# EMI_Shielding_Test.net
KiCad netlist of a schematic drawn in EAGLE
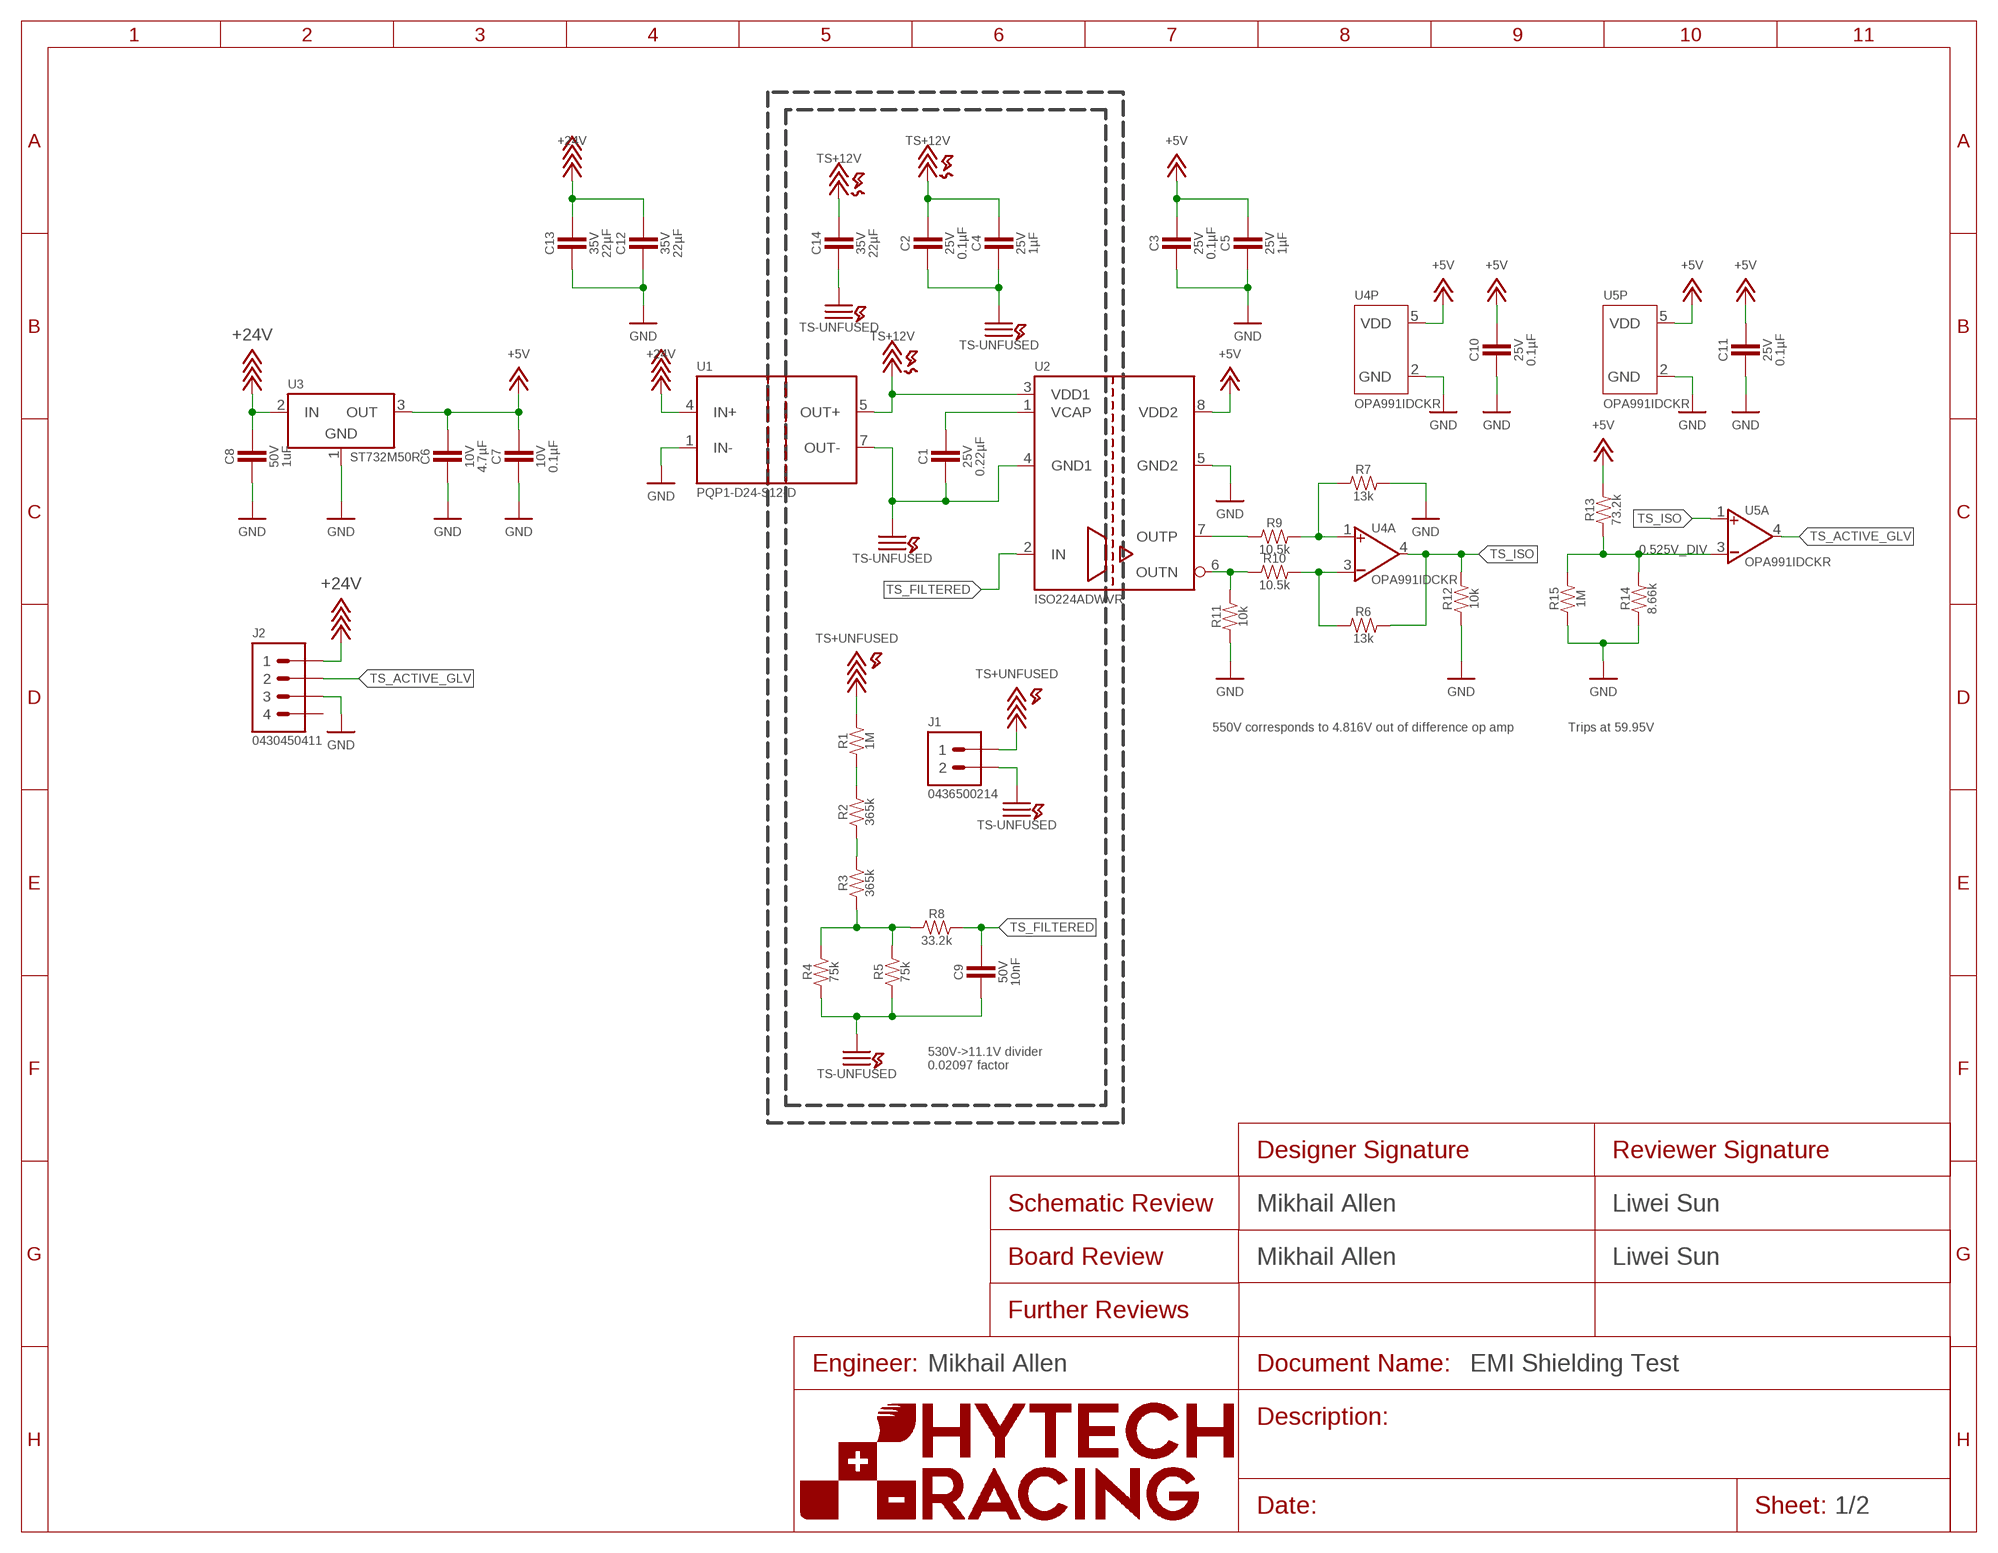
[diagram p0: schematic, sheet 1]
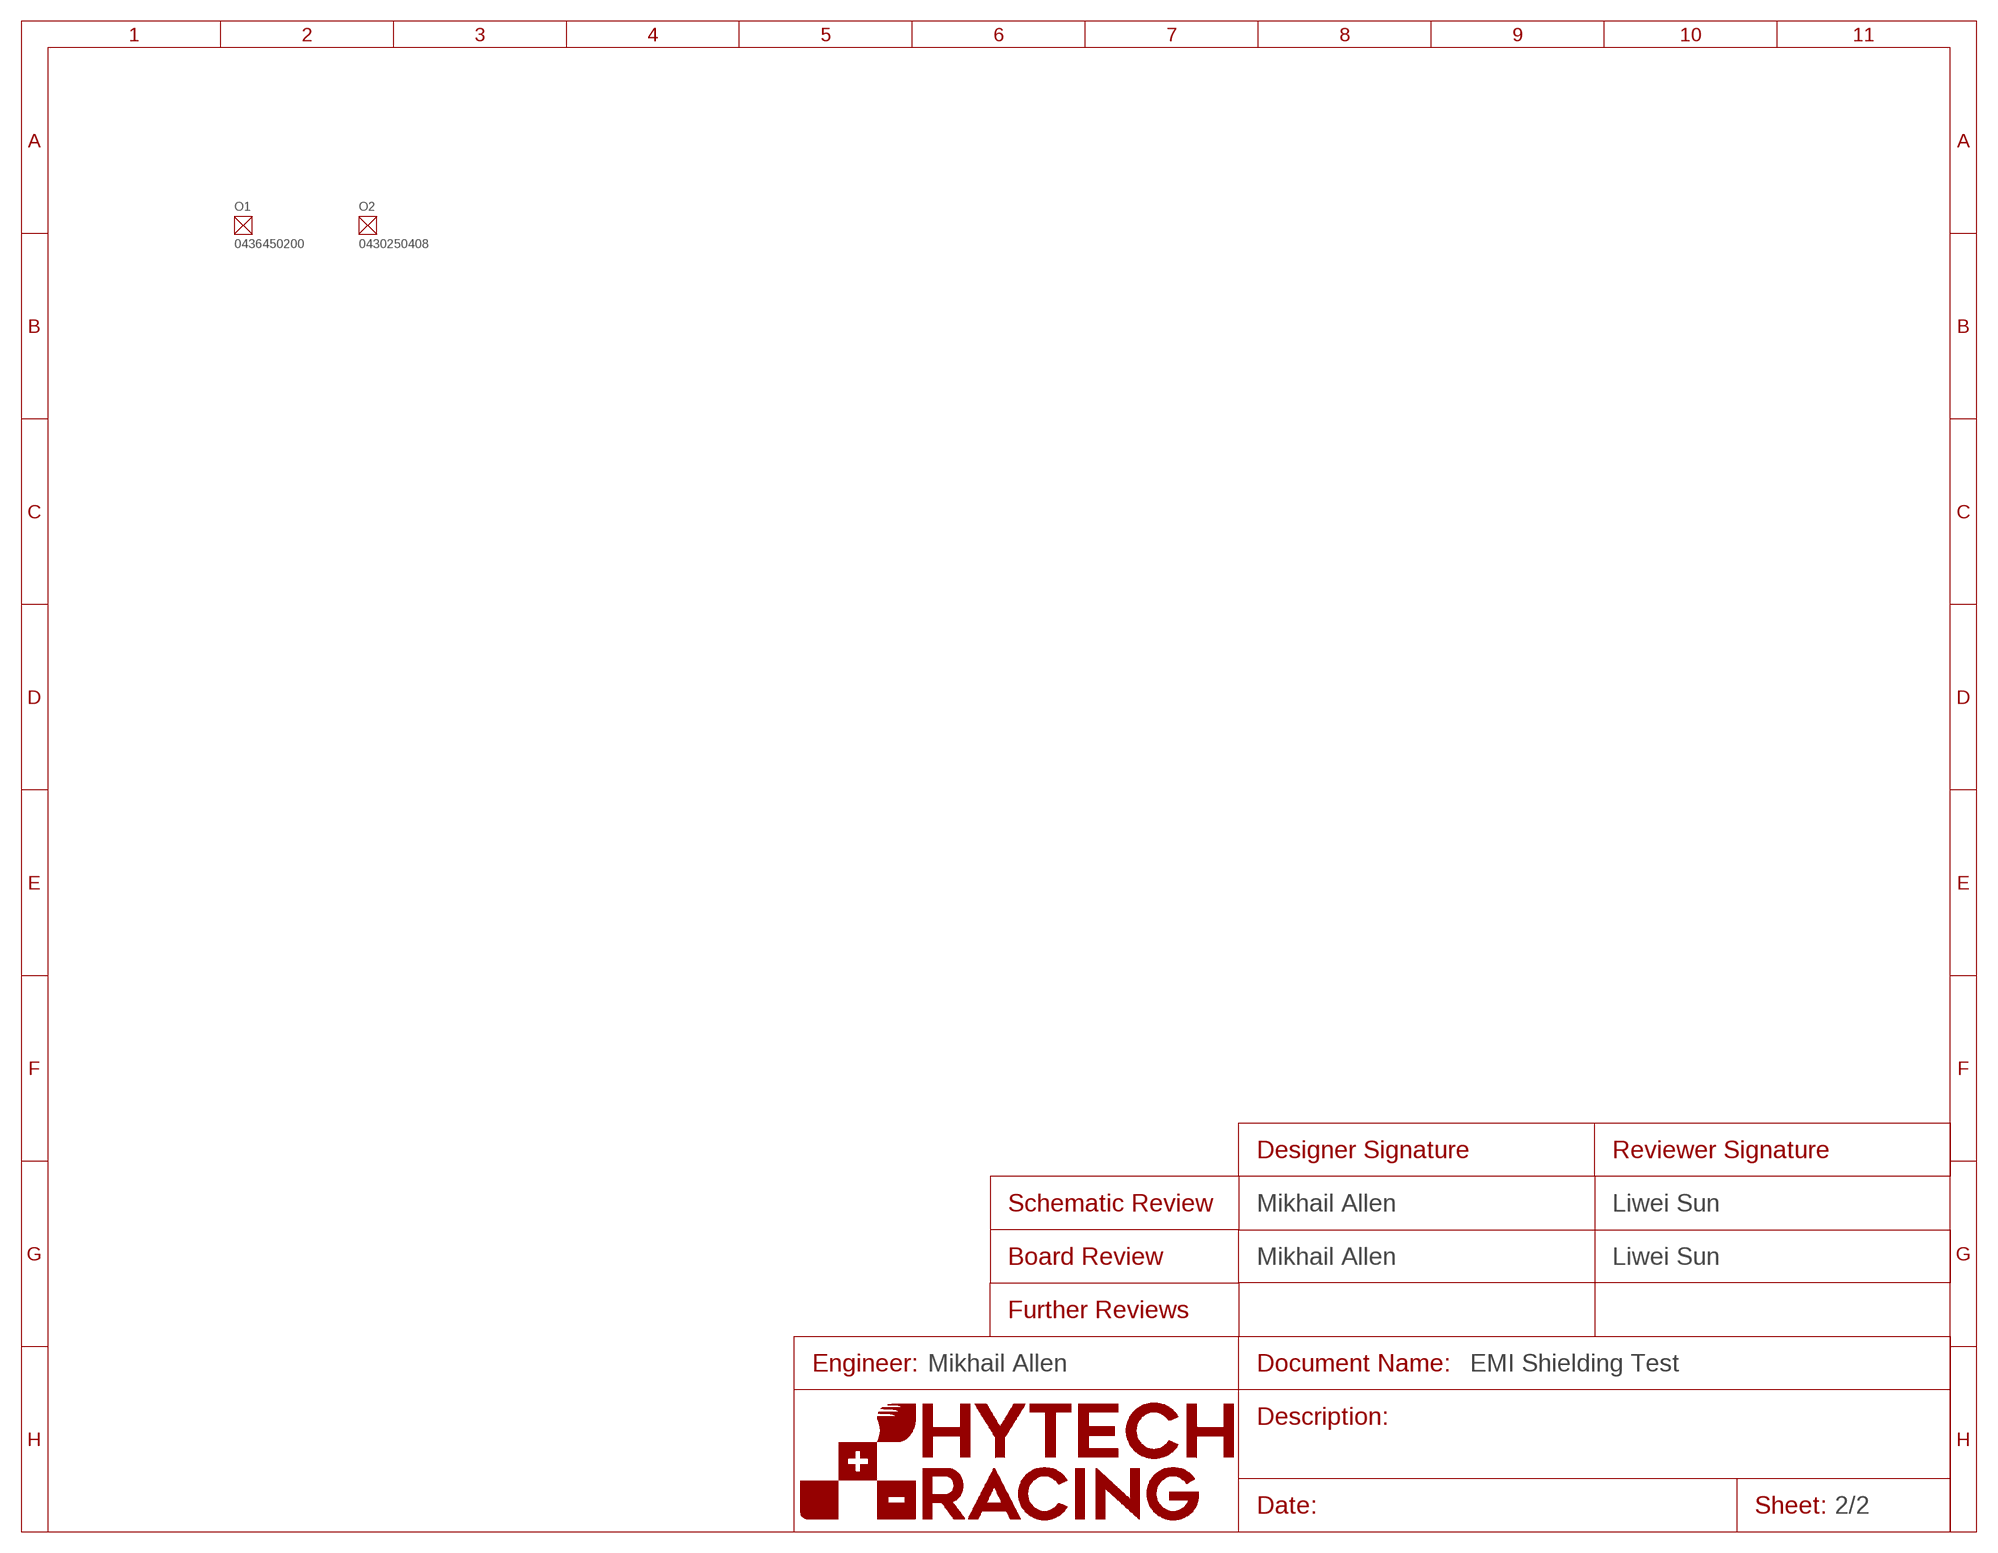
[diagram p1: schematic, sheet 2]

(export (version "E")
  (design (tool "Eeschema 10.0.6"))
  (components
    (comp (ref "C1")
      (value "CAPACITOR_0603_25V_0.22UF")
      (footprint "eagle-import:0603-CAP")
      (fields
        (field (name "CAPACITANCE") "0.22µF")
        (field (name "MANUFACTURER") "Walsin Technology Corporation")
        (field (name "MPN") "0603B224K250CT")
        (field (name "TOLERANCE") "10%")
        (field (name "VOLTAGE") "25V")
      )
      (libsource (lib "eagle-import") (part "CAPACITOR_?_060325V_0.22UF"))
    )
    (comp (ref "C2")
      (value "CAPACITOR_0603_25V_0.1UF")
      (footprint "eagle-import:0603-CAP")
      (fields
        (field (name "CAPACITANCE") "0.1µF")
        (field (name "MANUFACTURER") "Samsung Electro-Mechanics")
        (field (name "MPN") "CL10B104KA8NNNC")
        (field (name "TOLERANCE") "10%")
        (field (name "VOLTAGE") "25V")
      )
      (libsource (lib "eagle-import") (part "CAPACITOR_?_060325V_0.1UF"))
    )
    (comp (ref "C3")
      (value "CAPACITOR_0603_25V_0.1UF")
      (footprint "eagle-import:0603-CAP")
      (fields
        (field (name "CAPACITANCE") "0.1µF")
        (field (name "MANUFACTURER") "Samsung Electro-Mechanics")
        (field (name "MPN") "CL10B104KA8NNNC")
        (field (name "TOLERANCE") "10%")
        (field (name "VOLTAGE") "25V")
      )
      (libsource (lib "eagle-import") (part "CAPACITOR_?_060325V_0.1UF"))
    )
    (comp (ref "C4")
      (value "CAPACITOR_0603_25V_1UF")
      (footprint "eagle-import:0603-CAP")
      (fields
        (field (name "CAPACITANCE") "1µF")
        (field (name "MANUFACTURER") "Samsung Electro-Mechanics")
        (field (name "MPN") "CL10B105KA8NNNC")
        (field (name "TOLERANCE") "10%")
        (field (name "VOLTAGE") "25V")
      )
      (libsource (lib "eagle-import") (part "CAPACITOR_?_060325V_1UF"))
    )
    (comp (ref "C5")
      (value "CAPACITOR_0603_25V_1UF")
      (footprint "eagle-import:0603-CAP")
      (fields
        (field (name "CAPACITANCE") "1µF")
        (field (name "MANUFACTURER") "Samsung Electro-Mechanics")
        (field (name "MPN") "CL10B105KA8NNNC")
        (field (name "TOLERANCE") "10%")
        (field (name "VOLTAGE") "25V")
      )
      (libsource (lib "eagle-import") (part "CAPACITOR_?_060325V_1UF"))
    )
    (comp (ref "C6")
      (value "CAPACITOR_0603_10V_4.7UF")
      (footprint "eagle-import:0603-CAP")
      (fields
        (field (name "CAPACITANCE") "4.7µF")
        (field (name "MANUFACTURER") "Samsung Electro-Mechanics")
        (field (name "MPN") "CL10A475KP8NNNC")
        (field (name "TOLERANCE") "10%")
        (field (name "VOLTAGE") "10V")
      )
      (libsource (lib "eagle-import") (part "CAPACITOR_?_060310V_4.7UF"))
    )
    (comp (ref "C7")
      (value "CAPACITOR_0603_10V_0.1UF")
      (footprint "eagle-import:0603-CAP")
      (fields
        (field (name "CAPACITANCE") "0.1µF")
        (field (name "MANUFACTURER") "Vishay Vitramon")
        (field (name "MPN") "VJ0603Y104JXQPW1BC")
        (field (name "TOLERANCE") "5%")
        (field (name "VOLTAGE") "10V")
      )
      (libsource (lib "eagle-import") (part "CAPACITOR_?_060310V_0.1UF"))
    )
    (comp (ref "C8")
      (value "CAPACITOR_0603_50V_1UF")
      (footprint "eagle-import:0603-CAP")
      (fields
        (field (name "CAPACITANCE") "1uF")
        (field (name "MANUFACTURER") "Taiyo Yuden")
        (field (name "MPN") "UMK107BJ105KA-T")
        (field (name "TOLERANCE") "10%")
        (field (name "VOLTAGE") "50V")
      )
      (libsource (lib "eagle-import") (part "CAPACITOR_?_060350V_1UF"))
    )
    (comp (ref "C9")
      (value "CAPACITOR_0603_50V_10NF")
      (footprint "eagle-import:0603-CAP")
      (fields
        (field (name "CAPACITANCE") "10nF")
        (field (name "MANUFACTURER") "TDK Corporation")
        (field (name "MPN") "C1608C0G1H103J080AA")
        (field (name "TOLERANCE") "5%")
        (field (name "VOLTAGE") "50V")
      )
      (libsource (lib "eagle-import") (part "CAPACITOR_?_060350V_10NF"))
    )
    (comp (ref "C10")
      (value "CAPACITOR_0603_25V_0.1UF")
      (footprint "eagle-import:0603-CAP")
      (fields
        (field (name "CAPACITANCE") "0.1µF")
        (field (name "MANUFACTURER") "Samsung Electro-Mechanics")
        (field (name "MPN") "CL10B104KA8NNNC")
        (field (name "TOLERANCE") "10%")
        (field (name "VOLTAGE") "25V")
      )
      (libsource (lib "eagle-import") (part "CAPACITOR_?_060325V_0.1UF"))
    )
    (comp (ref "C11")
      (value "CAPACITOR_0603_25V_0.1UF")
      (footprint "eagle-import:0603-CAP")
      (fields
        (field (name "CAPACITANCE") "0.1µF")
        (field (name "MANUFACTURER") "Samsung Electro-Mechanics")
        (field (name "MPN") "CL10B104KA8NNNC")
        (field (name "TOLERANCE") "10%")
        (field (name "VOLTAGE") "25V")
      )
      (libsource (lib "eagle-import") (part "CAPACITOR_?_060325V_0.1UF"))
    )
    (comp (ref "C12")
      (value "CAPACITOR_1206_35V_22UF")
      (footprint "eagle-import:1206-CAP")
      (fields
        (field (name "CAPACITANCE") "22µF")
        (field (name "MANUFACTURER") "TDK Corporation")
        (field (name "MPN") "C3216X5R1V226M160AC")
        (field (name "TOLERANCE") "20%")
        (field (name "VOLTAGE") "35V")
      )
      (libsource (lib "eagle-import") (part "CAPACITOR_?_120635V_22UF"))
    )
    (comp (ref "C13")
      (value "CAPACITOR_1206_35V_22UF")
      (footprint "eagle-import:1206-CAP")
      (fields
        (field (name "CAPACITANCE") "22µF")
        (field (name "MANUFACTURER") "TDK Corporation")
        (field (name "MPN") "C3216X5R1V226M160AC")
        (field (name "TOLERANCE") "20%")
        (field (name "VOLTAGE") "35V")
      )
      (libsource (lib "eagle-import") (part "CAPACITOR_?_120635V_22UF"))
    )
    (comp (ref "C14")
      (value "CAPACITOR_1206_35V_22UF")
      (footprint "eagle-import:1206-CAP")
      (fields
        (field (name "CAPACITANCE") "22µF")
        (field (name "MANUFACTURER") "TDK Corporation")
        (field (name "MPN") "C3216X5R1V226M160AC")
        (field (name "TOLERANCE") "20%")
        (field (name "VOLTAGE") "35V")
      )
      (libsource (lib "eagle-import") (part "CAPACITOR_?_120635V_22UF"))
    )
    (comp (ref "J1")
      (value "CONNECTOR-2_MICROFIT_SMD_RIGHTANGLE_02_SINGLE_BLACK")
      (footprint "eagle-import:MOLEX_MICROFIT_SMD_RIGHTANGLE_02_SINGLE")
      (fields (field (name "MANUFACTURER") "Molex") (field (name "MPN") "0436500214"))
      (libsource (lib "eagle-import") (part "CONNECTOR-2_?_MICROFIT_SMD_RIGHTANGLE_02_SINGLEBLACK"))
    )
    (comp (ref "J2")
      (value "CONNECTOR-4_μF_S_RA_")
      (footprint "eagle-import:MOLEX_MICROFIT_SMD_RIGHTANGLE_04_DUAL")
      (fields (field (name "MPN") "0430450411") (field (name "MANUFACTURER") "Molex"))
      (libsource (lib "eagle-import") (part "CONNECTOR-4_?_μF_S_RA"))
    )
    (comp (ref "R1")
      (value "RESISTOR_0805_1M")
      (footprint "eagle-import:0805-RES")
      (fields
        (field (name "MANUFACTURER") "Panasonic Electronic Components")
        (field (name "MPN") "ERJ-PB6B1004V")
        (field (name "POWER") "0.25W")
        (field (name "RESISTANCE") "1M")
      )
      (libsource (lib "eagle-import") (part "RESISTOR_?_08051M"))
    )
    (comp (ref "R2")
      (value "RESISTOR_0805_365K")
      (footprint "eagle-import:0805-RES")
      (fields
        (field (name "MANUFACTURER") "Panasonic Electronic Components")
        (field (name "MPN") "ERJ-PB6B3653V")
        (field (name "POWER") "0.25W")
        (field (name "RESISTANCE") "365k")
      )
      (libsource (lib "eagle-import") (part "RESISTOR_?_0805365K"))
    )
    (comp (ref "R3")
      (value "RESISTOR_0805_365K")
      (footprint "eagle-import:0805-RES")
      (fields
        (field (name "MANUFACTURER") "Panasonic Electronic Components")
        (field (name "MPN") "ERJ-PB6B3653V")
        (field (name "POWER") "0.25W")
        (field (name "RESISTANCE") "365k")
      )
      (libsource (lib "eagle-import") (part "RESISTOR_?_0805365K"))
    )
    (comp (ref "R4")
      (value "RESISTOR_0805_HV75K")
      (footprint "eagle-import:0805-RES")
      (fields
        (field (name "MANUFACTURER") "Rohm Semiconductor")
        (field (name "MPN") "KTR10EZPF7502 ")
        (field (name "POWER") "0.125W")
        (field (name "RESISTANCE") "75k")
      )
      (libsource (lib "eagle-import") (part "RESISTOR_?_0805HV75K"))
    )
    (comp (ref "R5")
      (value "RESISTOR_0805_HV75K")
      (footprint "eagle-import:0805-RES")
      (fields
        (field (name "MANUFACTURER") "Rohm Semiconductor")
        (field (name "MPN") "KTR10EZPF7502 ")
        (field (name "POWER") "0.125W")
        (field (name "RESISTANCE") "75k")
      )
      (libsource (lib "eagle-import") (part "RESISTOR_?_0805HV75K"))
    )
    (comp (ref "R6")
      (value "RESISTOR_0603_13K")
      (footprint "eagle-import:0603-RES")
      (fields
        (field (name "MANUFACTURER") "Panasonic Electronic Components")
        (field (name "MPN") "ERA-3ARW133V")
        (field (name "POWER") "0.1W")
        (field (name "RESISTANCE") "13k")
      )
      (libsource (lib "eagle-import") (part "RESISTOR_?_060313K"))
    )
    (comp (ref "R7")
      (value "RESISTOR_0603_13K")
      (footprint "eagle-import:0603-RES")
      (fields
        (field (name "MANUFACTURER") "Panasonic Electronic Components")
        (field (name "MPN") "ERA-3ARW133V")
        (field (name "POWER") "0.1W")
        (field (name "RESISTANCE") "13k")
      )
      (libsource (lib "eagle-import") (part "RESISTOR_?_060313K"))
    )
    (comp (ref "R8")
      (value "RESISTOR_0603_33.2K")
      (footprint "eagle-import:0603-RES")
      (fields
        (field (name "MANUFACTURER") "Panasonic Electronic Components")
        (field (name "MPN") "ERJ-PB3B3322V")
        (field (name "POWER") "0.1W")
        (field (name "RESISTANCE") "33.2k")
      )
      (libsource (lib "eagle-import") (part "RESISTOR_?_060333.2K"))
    )
    (comp (ref "R9")
      (value "RESISTOR_0603_10.5K")
      (footprint "eagle-import:0603-RES")
      (fields
        (field (name "MANUFACTURER") "Panasonic Electronic Components")
        (field (name "MPN") "ERA-3AEB1052V")
        (field (name "POWER") "0.1W")
        (field (name "RESISTANCE") "10.5k")
      )
      (libsource (lib "eagle-import") (part "RESISTOR_?_060310.5K"))
    )
    (comp (ref "R10")
      (value "RESISTOR_0603_10.5K")
      (footprint "eagle-import:0603-RES")
      (fields
        (field (name "MANUFACTURER") "Panasonic Electronic Components")
        (field (name "MPN") "ERA-3AEB1052V")
        (field (name "POWER") "0.1W")
        (field (name "RESISTANCE") "10.5k")
      )
      (libsource (lib "eagle-import") (part "RESISTOR_?_060310.5K"))
    )
    (comp (ref "R11")
      (value "RESISTOR_0603_10K")
      (footprint "eagle-import:0603-RES")
      (fields
        (field (name "MANUFACTURER") "Panasonic Electronic Components")
        (field (name "MPN") "ERA-3ARB103V")
        (field (name "POWER") "0.1W")
        (field (name "RESISTANCE") "10k")
      )
      (libsource (lib "eagle-import") (part "RESISTOR_?_060310K"))
    )
    (comp (ref "R12")
      (value "RESISTOR_0603_10K")
      (footprint "eagle-import:0603-RES")
      (fields
        (field (name "MANUFACTURER") "Panasonic Electronic Components")
        (field (name "MPN") "ERA-3ARB103V")
        (field (name "POWER") "0.1W")
        (field (name "RESISTANCE") "10k")
      )
      (libsource (lib "eagle-import") (part "RESISTOR_?_060310K"))
    )
    (comp (ref "R13")
      (value "RESISTOR_0603_73.2K")
      (footprint "eagle-import:0603-RES")
      (fields
        (field (name "MANUFACTURER") "Panasonic Electronic Components")
        (field (name "MPN") "ERA-3AEB7322V")
        (field (name "POWER") "0.1W")
        (field (name "RESISTANCE") "73.2k")
      )
      (libsource (lib "eagle-import") (part "RESISTOR_?_060373.2K"))
    )
    (comp (ref "R14")
      (value "RESISTOR_0603_8.66K")
      (footprint "eagle-import:0603-RES")
      (fields
        (field (name "MANUFACTURER") "Yageo")
        (field (name "MPN") "RT0603BRD078K66L")
        (field (name "POWER") "0.1W")
        (field (name "RESISTANCE") "8.66k")
      )
      (libsource (lib "eagle-import") (part "RESISTOR_?_06038.66K"))
    )
    (comp (ref "R15")
      (value "RESISTOR_0603_1M")
      (footprint "eagle-import:0603-RES")
      (fields
        (field (name "MANUFACTURER") "Yageo")
        (field (name "MPN") "RC0603FR-071ML")
        (field (name "POWER") "0.1W")
        (field (name "RESISTANCE") "1M")
      )
      (libsource (lib "eagle-import") (part "RESISTOR_?_06031M"))
    )
    (comp (ref "U1")
      (value "VOLTAGE_REGULATOR_ISO_PQP1-D_")
      (footprint "eagle-import:PQP1-D")
      (fields (field (name "MANUFACTURER") "CUI Inc.") (field (name "MPN") "PQP1-D24-S12-D"))
      (libsource (lib "eagle-import") (part "VOLTAGE_REGULATOR_ISO_?_PQP1-DD24-S12"))
    )
    (comp (ref "U2")
      (value "ISO224A_AIRGAP")
      (footprint "eagle-import:SOIC-08(WIDE,0.295_)-AIRGAP")
      (fields (field (name "MANUFACTURER") "Texas Instruments") (field (name "MPN") "ISO224ADWVR"))
      (libsource (lib "eagle-import") (part "ISO224_AIRGAPA"))
    )
    (comp (ref "U3")
      (value "VOLTAGE_REGULATOR_SOT-23-5_5V")
      (footprint "eagle-import:SOT-23-5")
      (fields (field (name "MANUFACTURER") "STMicroelectronics") (field (name "MPN") "ST732M50R"))
      (libsource (lib "eagle-import") (part "VOLTAGE_REGULATOR_?_SOT-23-55V"))
    )
    (comp (ref "U4")
      (value "OPAMP_1_CHANNEL_OPA991")
      (footprint "eagle-import:SC-70-5")
      (fields (field (name "MANUFACTURER") "Texas Instruments") (field (name "MPN") "OPA991IDCKR"))
      (libsource (lib "eagle-import") (part "OPAMP_1_CHANNEL_OPA991"))
    )
    (comp (ref "U5")
      (value "OPAMP_1_CHANNEL_OPA991")
      (footprint "eagle-import:SC-70-5")
      (fields (field (name "MANUFACTURER") "Texas Instruments") (field (name "MPN") "OPA991IDCKR"))
      (libsource (lib "eagle-import") (part "OPAMP_1_CHANNEL_OPA991"))
    )
  )
  (nets
    (net (code "1") (name "+24V") (class "Default")
      (node (ref "C12") (pin "1") (pinfunction "1_1") (pintype "passive"))
      (node (ref "C13") (pin "1") (pinfunction "1_1") (pintype "passive"))
      (node (ref "C8") (pin "1") (pinfunction "1_1") (pintype "passive"))
      (node (ref "J2") (pin "1") (pinfunction "1_1") (pintype "passive"))
      (node (ref "U1") (pin "4") (pinfunction "IN+_4") (pintype "power_in"))
      (node (ref "U3") (pin "2") (pinfunction "IN_2") (pintype "power_in"))
    )
    (net (code "2") (name "0.525V_DIV") (class "Default")
      (node (ref "R13") (pin "1") (pinfunction "1_1") (pintype "passive"))
      (node (ref "R14") (pin "2") (pinfunction "2_2") (pintype "passive"))
      (node (ref "R15") (pin "2") (pinfunction "2_2") (pintype "passive"))
      (node (ref "U5") (pin "3") (pinfunction "VIN-_3") (pintype "input"))
    )
    (net (code "3") (name "GND") (class "Default")
      (node (ref "C10") (pin "2") (pinfunction "2_2") (pintype "passive"))
      (node (ref "C11") (pin "2") (pinfunction "2_2") (pintype "passive"))
      (node (ref "C12") (pin "2") (pinfunction "2_2") (pintype "passive"))
      (node (ref "C13") (pin "2") (pinfunction "2_2") (pintype "passive"))
      (node (ref "C3") (pin "2") (pinfunction "2_2") (pintype "passive"))
      (node (ref "C5") (pin "2") (pinfunction "2_2") (pintype "passive"))
      (node (ref "C6") (pin "2") (pinfunction "2_2") (pintype "passive"))
      (node (ref "C7") (pin "2") (pinfunction "2_2") (pintype "passive"))
      (node (ref "C8") (pin "2") (pinfunction "2_2") (pintype "passive"))
      (node (ref "J2") (pin "3") (pinfunction "3_3") (pintype "passive"))
      (node (ref "R11") (pin "1") (pinfunction "1_1") (pintype "passive"))
      (node (ref "R12") (pin "1") (pinfunction "1_1") (pintype "passive"))
      (node (ref "R14") (pin "1") (pinfunction "1_1") (pintype "passive"))
      (node (ref "R15") (pin "1") (pinfunction "1_1") (pintype "passive"))
      (node (ref "R7") (pin "2") (pinfunction "2_2") (pintype "passive"))
      (node (ref "U1") (pin "1") (pinfunction "IN-_1") (pintype "power_in"))
      (node (ref "U2") (pin "5") (pinfunction "GND2_5") (pintype "power_in"))
      (node (ref "U3") (pin "1") (pinfunction "GND_1") (pintype "power_in"))
      (node (ref "U4") (pin "2") (pinfunction "GND_2") (pintype "power_in"))
      (node (ref "U5") (pin "2") (pinfunction "GND_2") (pintype "power_in"))
    )
    (net (code "4") (name "Net-(R1-Pad1)") (class "Default")
      (node (ref "R1") (pin "1") (pinfunction "1_1") (pintype "passive"))
      (node (ref "R2") (pin "2") (pinfunction "2_2") (pintype "passive"))
    )
    (net (code "5") (name "Net-(R2-Pad1)") (class "Default")
      (node (ref "R2") (pin "1") (pinfunction "1_1") (pintype "passive"))
      (node (ref "R3") (pin "2") (pinfunction "2_2") (pintype "passive"))
    )
    (net (code "6") (name "Net-(R3-Pad1)") (class "Default")
      (node (ref "R3") (pin "1") (pinfunction "1_1") (pintype "passive"))
      (node (ref "R4") (pin "2") (pinfunction "2_2") (pintype "passive"))
      (node (ref "R5") (pin "2") (pinfunction "2_2") (pintype "passive"))
      (node (ref "R8") (pin "1") (pinfunction "1_1") (pintype "passive"))
    )
    (net (code "7") (name "Net-(U2-OUTN)") (class "Default")
      (node (ref "R10") (pin "1") (pinfunction "1_1") (pintype "passive"))
      (node (ref "R11") (pin "2") (pinfunction "2_2") (pintype "passive"))
      (node (ref "U2") (pin "6") (pinfunction "OUTN_6") (pintype "output"))
    )
    (net (code "8") (name "Net-(U2-OUTP)") (class "Default")
      (node (ref "R9") (pin "1") (pinfunction "1_1") (pintype "passive"))
      (node (ref "U2") (pin "7") (pinfunction "OUTP_7") (pintype "output"))
    )
    (net (code "9") (name "Net-(U2-VCAP)") (class "Default")
      (node (ref "C1") (pin "1") (pinfunction "1_1") (pintype "passive"))
      (node (ref "U2") (pin "1") (pinfunction "VCAP_1") (pintype "passive"))
    )
    (net (code "10") (name "Net-(U4A-VIN+)") (class "Default")
      (node (ref "R7") (pin "1") (pinfunction "1_1") (pintype "passive"))
      (node (ref "R9") (pin "2") (pinfunction "2_2") (pintype "passive"))
      (node (ref "U4") (pin "1") (pinfunction "VIN+_1") (pintype "input"))
    )
    (net (code "11") (name "Net-(U4A-VIN-)") (class "Default")
      (node (ref "R10") (pin "2") (pinfunction "2_2") (pintype "passive"))
      (node (ref "R6") (pin "1") (pinfunction "1_1") (pintype "passive"))
      (node (ref "U4") (pin "3") (pinfunction "VIN-_3") (pintype "input"))
    )
    (net (code "12") (name "TS+12V") (class "Default")
      (node (ref "C14") (pin "1") (pinfunction "1_1") (pintype "passive"))
      (node (ref "C2") (pin "1") (pinfunction "1_1") (pintype "passive"))
      (node (ref "C4") (pin "1") (pinfunction "1_1") (pintype "passive"))
      (node (ref "U1") (pin "5") (pinfunction "OUT+_5") (pintype "power_in"))
      (node (ref "U2") (pin "3") (pinfunction "VDD1_3") (pintype "power_in"))
    )
    (net (code "13") (name "TS+UNFUSED") (class "Default")
      (node (ref "J1") (pin "1") (pinfunction "1_1") (pintype "passive"))
      (node (ref "R1") (pin "2") (pinfunction "2_2") (pintype "passive"))
    )
    (net (code "14") (name "TS-UNFUSED") (class "Default")
      (node (ref "C1") (pin "2") (pinfunction "2_2") (pintype "passive"))
      (node (ref "C14") (pin "2") (pinfunction "2_2") (pintype "passive"))
      (node (ref "C2") (pin "2") (pinfunction "2_2") (pintype "passive"))
      (node (ref "C4") (pin "2") (pinfunction "2_2") (pintype "passive"))
      (node (ref "C9") (pin "2") (pinfunction "2_2") (pintype "passive"))
      (node (ref "J1") (pin "2") (pinfunction "2_2") (pintype "passive"))
      (node (ref "R4") (pin "1") (pinfunction "1_1") (pintype "passive"))
      (node (ref "R5") (pin "1") (pinfunction "1_1") (pintype "passive"))
      (node (ref "U1") (pin "7") (pinfunction "OUT-_7") (pintype "power_in"))
      (node (ref "U2") (pin "4") (pinfunction "GND1_4") (pintype "power_in"))
    )
    (net (code "15") (name "TS_ACTIVE_GLV") (class "Default")
      (node (ref "J2") (pin "2") (pinfunction "2_2") (pintype "passive"))
      (node (ref "U5") (pin "4") (pinfunction "VOUT_4") (pintype "output"))
    )
    (net (code "16") (name "TS_FILTERED") (class "Default")
      (node (ref "C9") (pin "1") (pinfunction "1_1") (pintype "passive"))
      (node (ref "R8") (pin "2") (pinfunction "2_2") (pintype "passive"))
      (node (ref "U2") (pin "2") (pinfunction "IN_2") (pintype "input"))
    )
    (net (code "17") (name "TS_ISO") (class "Default")
      (node (ref "R12") (pin "2") (pinfunction "2_2") (pintype "passive"))
      (node (ref "R6") (pin "2") (pinfunction "2_2") (pintype "passive"))
      (node (ref "U4") (pin "4") (pinfunction "VOUT_4") (pintype "output"))
      (node (ref "U5") (pin "1") (pinfunction "VIN+_1") (pintype "input"))
    )
    (net (code "18") (name "VDD") (class "Default")
      (node (ref "C10") (pin "1") (pinfunction "1_1") (pintype "passive"))
      (node (ref "C11") (pin "1") (pinfunction "1_1") (pintype "passive"))
      (node (ref "C3") (pin "1") (pinfunction "1_1") (pintype "passive"))
      (node (ref "C5") (pin "1") (pinfunction "1_1") (pintype "passive"))
      (node (ref "C6") (pin "1") (pinfunction "1_1") (pintype "passive"))
      (node (ref "C7") (pin "1") (pinfunction "1_1") (pintype "passive"))
      (node (ref "R13") (pin "2") (pinfunction "2_2") (pintype "passive"))
      (node (ref "U2") (pin "8") (pinfunction "VDD2_8") (pintype "power_in"))
      (node (ref "U3") (pin "3") (pinfunction "OUT_3") (pintype "power_in"))
      (node (ref "U4") (pin "5") (pinfunction "VDD_5") (pintype "power_in"))
      (node (ref "U5") (pin "5") (pinfunction "VDD_5") (pintype "power_in"))
    )
    (net (code "19") (name "unconnected-(J2-Pad4)") (class "Default")
      (node (ref "J2") (pin "4") (pinfunction "4_4") (pintype "passive"))
    )
  )
)
